# led_driver_12v_1a_round.net
KiCad netlist of a schematic drawn in EAGLE
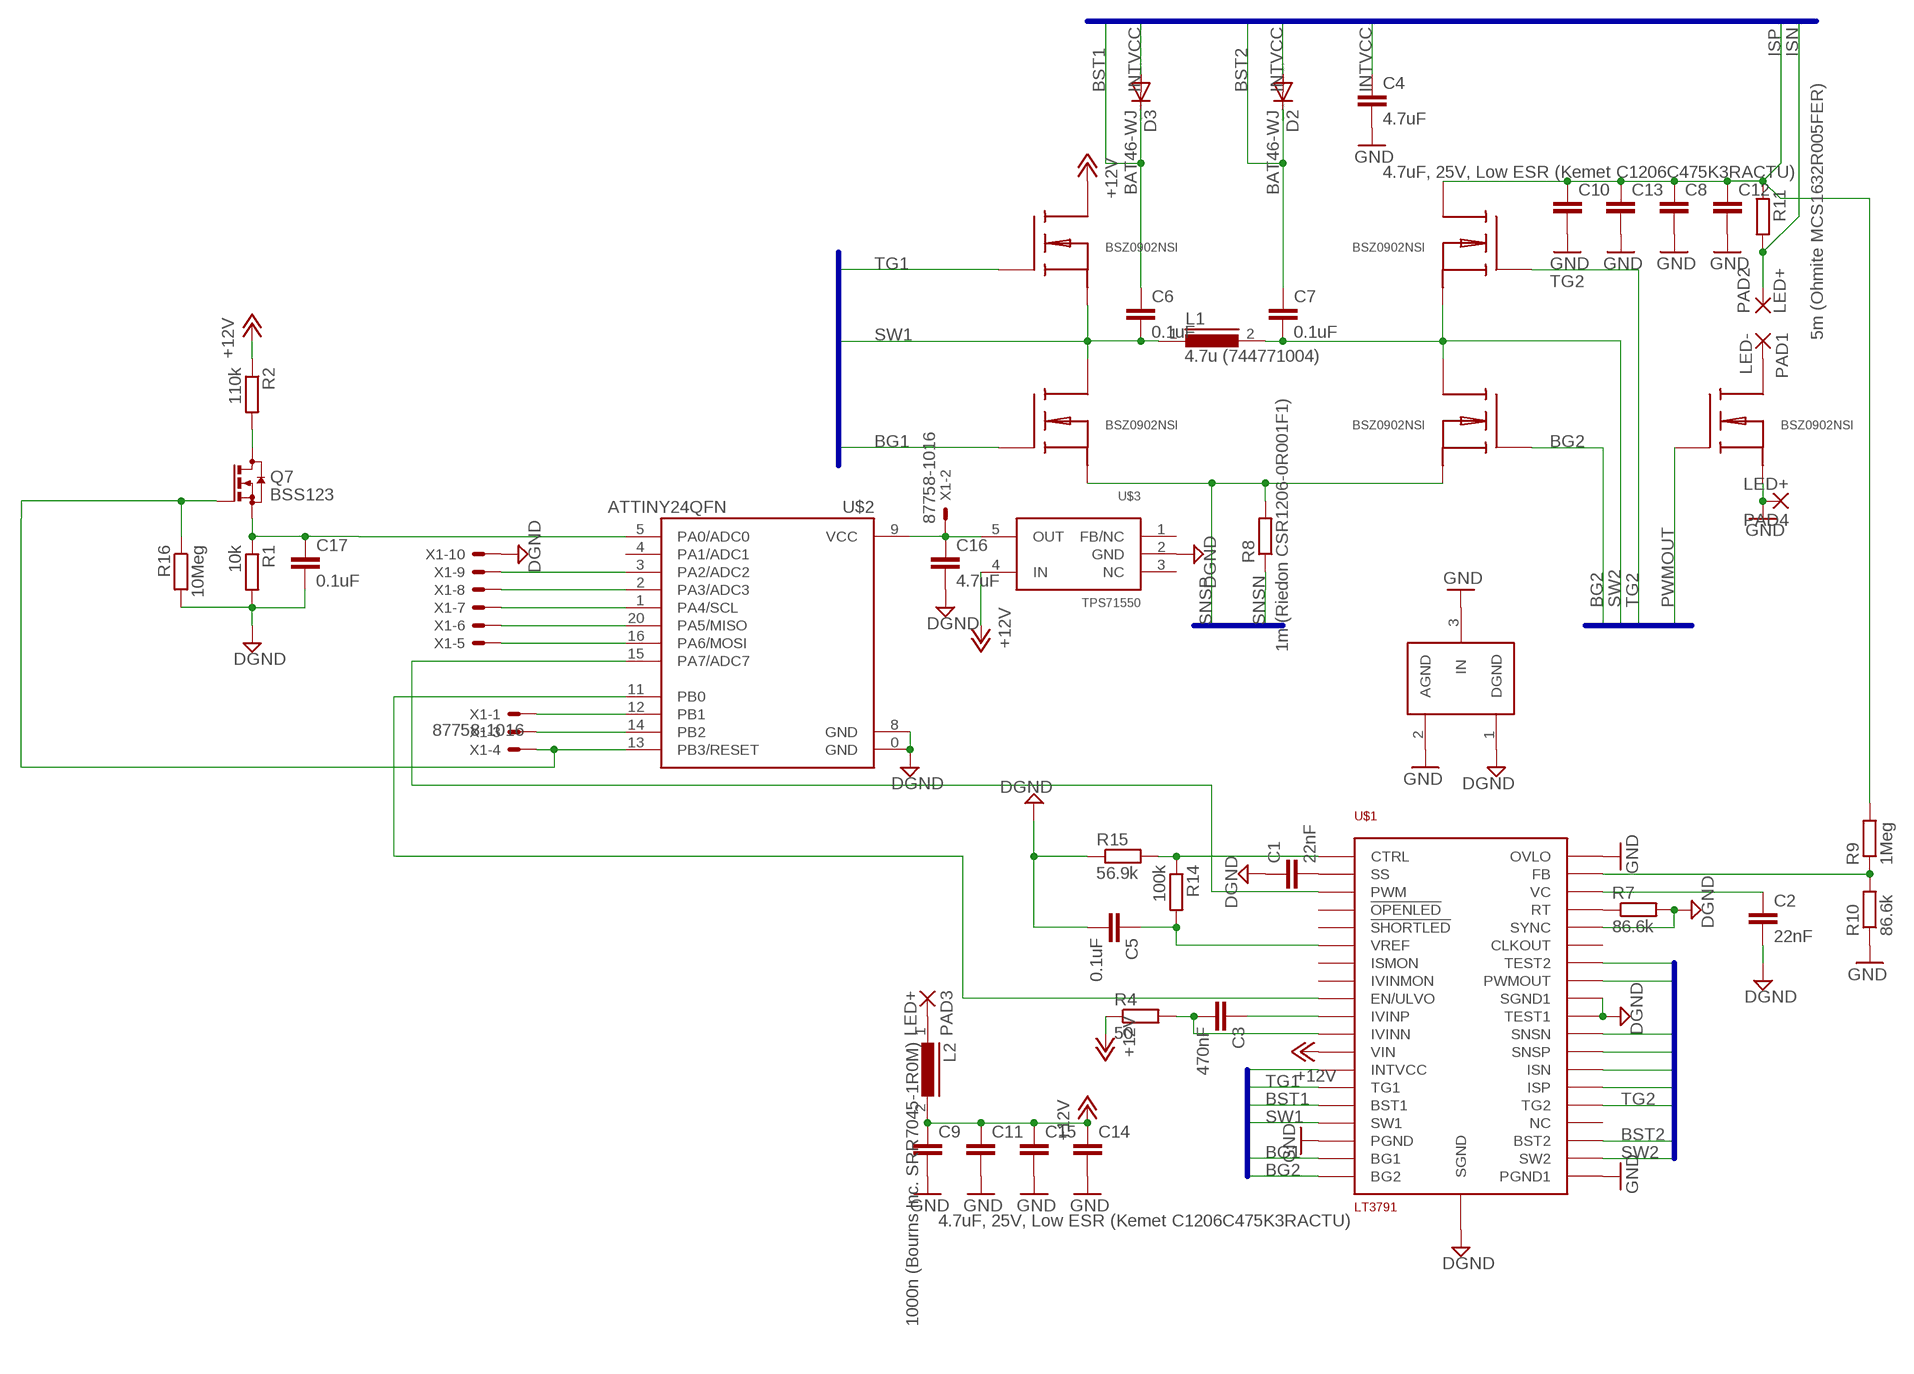
[diagram p0: schematic, sheet 1]

(export (version "E")
  (design (tool "Eeschema 10.0.6"))
  (components
    (comp (ref "C1")
      (value "22nF")
      (footprint "eagle-import:C0402")
      (libsource (lib "eagle-import") (part "resistor_C-EUC0402"))
    )
    (comp (ref "C2")
      (value "22nF")
      (footprint "eagle-import:C0402K")
      (libsource (lib "eagle-import") (part "resistor_C-EUC0402K"))
    )
    (comp (ref "C3")
      (value "470nF")
      (footprint "eagle-import:C0402K")
      (libsource (lib "eagle-import") (part "resistor_C-EUC0402K"))
    )
    (comp (ref "C4")
      (value "4.7uF")
      (footprint "eagle-import:C1206")
      (libsource (lib "eagle-import") (part "C-EUC1206"))
    )
    (comp (ref "C5")
      (value "0.1uF")
      (footprint "eagle-import:C0402K")
      (libsource (lib "eagle-import") (part "resistor_C-EUC0402K"))
    )
    (comp (ref "C6")
      (value "0.1uF")
      (footprint "eagle-import:C0402K")
      (libsource (lib "eagle-import") (part "resistor_C-EUC0402K"))
    )
    (comp (ref "C7")
      (value "0.1uF")
      (footprint "eagle-import:C0402K")
      (libsource (lib "eagle-import") (part "resistor_C-EUC0402K"))
    )
    (comp (ref "C8")
      (value "4.7uF, 25V, Low ESR (Kemet C1206C475K3RACTU)")
      (footprint "eagle-import:C1206")
      (libsource (lib "eagle-import") (part "C-EUC1206"))
    )
    (comp (ref "C9")
      (value "4.7uF, 25V, Low ESR (Kemet C1206C475K3RACTU)")
      (footprint "eagle-import:C1206")
      (libsource (lib "eagle-import") (part "C-EUC1206"))
    )
    (comp (ref "C10")
      (value "4.7uF, 25V, Low ESR (Kemet C1206C475K3RACTU)")
      (footprint "eagle-import:C1206")
      (libsource (lib "eagle-import") (part "C-EUC1206"))
    )
    (comp (ref "C11")
      (value "4.7uF, 25V, Low ESR (Kemet C1206C475K3RACTU)")
      (footprint "eagle-import:C1206")
      (libsource (lib "eagle-import") (part "C-EUC1206"))
    )
    (comp (ref "C12")
      (value "4.7uF, 25V, Low ESR (Kemet C1206C475K3RACTU)")
      (footprint "eagle-import:C1206")
      (libsource (lib "eagle-import") (part "C-EUC1206"))
    )
    (comp (ref "C13")
      (value "4.7uF, 25V, Low ESR (Kemet C1206C475K3RACTU)")
      (footprint "eagle-import:C1206")
      (libsource (lib "eagle-import") (part "C-EUC1206"))
    )
    (comp (ref "C14")
      (value "4.7uF, 25V, Low ESR (Kemet C1206C475K3RACTU)")
      (footprint "eagle-import:C1206")
      (libsource (lib "eagle-import") (part "C-EUC1206"))
    )
    (comp (ref "C15")
      (value "4.7uF, 25V, Low ESR (Kemet C1206C475K3RACTU)")
      (footprint "eagle-import:C1206")
      (libsource (lib "eagle-import") (part "C-EUC1206"))
    )
    (comp (ref "C16")
      (value "4.7uF")
      (footprint "eagle-import:C1206")
      (libsource (lib "eagle-import") (part "C-EUC1206"))
    )
    (comp (ref "C17")
      (value "0.1uF")
      (footprint "eagle-import:C0402K")
      (libsource (lib "eagle-import") (part "resistor_C-EUC0402K"))
    )
    (comp (ref "D2")
      (value "BAT46-WJ")
      (footprint "eagle-import:SOD323-W")
      (libsource (lib "eagle-import") (part "DIODE-SOD323-W"))
    )
    (comp (ref "D3")
      (value "BAT46-WJ")
      (footprint "eagle-import:SOD323-W")
      (libsource (lib "eagle-import") (part "DIODE-SOD323-W"))
    )
    (comp (ref "L1")
      (value "4.7u (744771004)")
      (footprint "eagle-import:DR127")
      (libsource (lib "eagle-import") (part "DR127"))
    )
    (comp (ref "L2")
      (value "1000n (Bourns Inc. SRR7045-1R0M)")
      (footprint "eagle-import:DR74")
      (libsource (lib "eagle-import") (part "DR74"))
    )
    (comp (ref "PAD1")
      (value "LED-")
      (footprint "eagle-import:3,81_1,4")
      (libsource (lib "eagle-import") (part "WIREPAD3,81/1,4"))
    )
    (comp (ref "PAD2")
      (value "LED+")
      (footprint "eagle-import:3,81_1,4")
      (libsource (lib "eagle-import") (part "WIREPAD3,81/1,4"))
    )
    (comp (ref "PAD3")
      (value "LED+")
      (footprint "eagle-import:5-2,5")
      (libsource (lib "eagle-import") (part "WIREPADSMD5-2,5"))
    )
    (comp (ref "PAD4")
      (value "LED+")
      (footprint "eagle-import:5-2,5")
      (libsource (lib "eagle-import") (part "WIREPADSMD5-2,5"))
    )
    (comp (ref "Q1")
      (value "BSZ0902NSI")
      (footprint "eagle-import:BSZ090X")
      (libsource (lib "eagle-import") (part "BSZ090X"))
    )
    (comp (ref "Q2")
      (value "BSZ0902NSI")
      (footprint "eagle-import:BSZ090X")
      (libsource (lib "eagle-import") (part "BSZ090X"))
    )
    (comp (ref "Q3")
      (value "BSZ0902NSI")
      (footprint "eagle-import:BSZ090X")
      (libsource (lib "eagle-import") (part "BSZ090X"))
    )
    (comp (ref "Q4")
      (value "BSZ0902NSI")
      (footprint "eagle-import:BSZ090X")
      (libsource (lib "eagle-import") (part "BSZ090X"))
    )
    (comp (ref "Q5")
      (value "BSZ0902NSI")
      (footprint "eagle-import:BSZ090X")
      (libsource (lib "eagle-import") (part "BSZ090X"))
    )
    (comp (ref "Q7")
      (value "BSS123")
      (footprint "eagle-import:SOT23")
      (libsource (lib "eagle-import") (part "BSS123"))
    )
    (comp (ref "R1")
      (value "10k")
      (footprint "eagle-import:R0402")
      (libsource (lib "eagle-import") (part "R-EU_R0402"))
    )
    (comp (ref "R2")
      (value "110k")
      (footprint "eagle-import:R0402")
      (libsource (lib "eagle-import") (part "R-EU_R0402"))
    )
    (comp (ref "R4")
      (value "50")
      (footprint "eagle-import:R0402")
      (libsource (lib "eagle-import") (part "R-EU_R0402"))
    )
    (comp (ref "R7")
      (value "86.6k")
      (footprint "eagle-import:R0402")
      (libsource (lib "eagle-import") (part "R-EU_R0402"))
    )
    (comp (ref "R8")
      (value "1m (Riedon CSR1206-0R001F1)")
      (footprint "eagle-import:R1206")
      (libsource (lib "eagle-import") (part "R-EU_R1206"))
    )
    (comp (ref "R9")
      (value "1Meg")
      (footprint "eagle-import:R0402")
      (libsource (lib "eagle-import") (part "R-EU_R0402"))
    )
    (comp (ref "R10")
      (value "86.6k")
      (footprint "eagle-import:R0402")
      (libsource (lib "eagle-import") (part "R-EU_R0402"))
    )
    (comp (ref "R11")
      (value "5m (Ohmite MCS1632R005FER)")
      (footprint "eagle-import:R1206")
      (libsource (lib "eagle-import") (part "R-EU_R1206"))
    )
    (comp (ref "R14")
      (value "100k")
      (footprint "eagle-import:R0402")
      (libsource (lib "eagle-import") (part "R-EU_R0402"))
    )
    (comp (ref "R15")
      (value "56.9k")
      (footprint "eagle-import:R0402")
      (libsource (lib "eagle-import") (part "R-EU_R0402"))
    )
    (comp (ref "R16")
      (value "10Meg")
      (footprint "eagle-import:R0402")
      (libsource (lib "eagle-import") (part "R-EU_R0402"))
    )
    (comp (ref "U$1")
      (value "LT3791")
      (footprint "eagle-import:TSSOP38")
      (libsource (lib "eagle-import") (part "LT3791"))
    )
    (comp (ref "U$2")
      (value "ATTINY24QFN")
      (footprint "eagle-import:QFN20")
      (libsource (lib "eagle-import") (part "ATTINY24QFN"))
    )
    (comp (ref "U$3")
      (value "TPS71550")
      (footprint "eagle-import:SC70")
      (libsource (lib "eagle-import") (part "TPS715"))
    )
    (comp (ref "U$4")
      (value "GND_CONNECT")
      (footprint "eagle-import:GND_CONNECT")
      (libsource (lib "eagle-import") (part "GND_CONNECT"))
    )
    (comp (ref "X1")
      (value "87758-1016")
      (footprint "eagle-import:87758-1016")
      (fields (field (name "MF") "MOLEX"))
      (libsource (lib "eagle-import") (part "87758-1016"))
    )
  )
  (nets
    (net (code "1") (name "+12V") (class "Default")
      (node (ref "C11") (pin "1") (pinfunction "1_1") (pintype "passive"))
      (node (ref "C14") (pin "1") (pinfunction "1_1") (pintype "passive"))
      (node (ref "C15") (pin "1") (pinfunction "1_1") (pintype "passive"))
      (node (ref "C9") (pin "1") (pinfunction "1_1") (pintype "passive"))
      (node (ref "L2") (pin "2") (pinfunction "2_2") (pintype "passive"))
      (node (ref "Q1") (pin "D") (pinfunction "D_D") (pintype "bidirectional"))
      (node (ref "Q1") (pin "D@1") (pinfunction "D_D@1") (pintype "bidirectional"))
      (node (ref "Q1") (pin "D@2") (pinfunction "D_D@2") (pintype "bidirectional"))
      (node (ref "Q1") (pin "D@3") (pinfunction "D_D@3") (pintype "bidirectional"))
      (node (ref "Q1") (pin "D@4") (pinfunction "D_D@4") (pintype "bidirectional"))
      (node (ref "R2") (pin "1") (pinfunction "1_1") (pintype "passive"))
      (node (ref "R4") (pin "1") (pinfunction "1_1") (pintype "passive"))
      (node (ref "U$1") (pin "P$12") (pinfunction "VIN_P$12") (pintype "bidirectional"))
      (node (ref "U$3") (pin "4") (pinfunction "IN_4") (pintype "bidirectional"))
    )
    (net (code "3") (name "BG1") (class "Default")
      (node (ref "Q2") (pin "G") (pinfunction "G_G") (pintype "bidirectional"))
      (node (ref "U$1") (pin "P$18") (pinfunction "BG1_P$18") (pintype "bidirectional"))
    )
    (net (code "4") (name "BG2") (class "Default")
      (node (ref "Q3") (pin "G") (pinfunction "G_G") (pintype "bidirectional"))
      (node (ref "U$1") (pin "P$19") (pinfunction "BG2_P$19") (pintype "bidirectional"))
    )
    (net (code "5") (name "BST1") (class "Default")
      (node (ref "C6") (pin "1") (pinfunction "1_1") (pintype "passive"))
      (node (ref "D3") (pin "C") (pinfunction "C_C") (pintype "passive"))
      (node (ref "U$1") (pin "P$15") (pinfunction "BST1_P$15") (pintype "bidirectional"))
    )
    (net (code "6") (name "BST2") (class "Default")
      (node (ref "C7") (pin "1") (pinfunction "1_1") (pintype "passive"))
      (node (ref "D2") (pin "C") (pinfunction "C_C") (pintype "passive"))
      (node (ref "U$1") (pin "P$22") (pinfunction "BST2_P$22") (pintype "bidirectional"))
    )
    (net (code "7") (name "DGND") (class "Default")
      (node (ref "C1") (pin "1") (pinfunction "1_1") (pintype "passive"))
      (node (ref "C16") (pin "2") (pinfunction "2_2") (pintype "passive"))
      (node (ref "C17") (pin "2") (pinfunction "2_2") (pintype "passive"))
      (node (ref "C2") (pin "2") (pinfunction "2_2") (pintype "passive"))
      (node (ref "C5") (pin "2") (pinfunction "2_2") (pintype "passive"))
      (node (ref "R1") (pin "2") (pinfunction "2_2") (pintype "passive"))
      (node (ref "R15") (pin "1") (pinfunction "1_1") (pintype "passive"))
      (node (ref "R16") (pin "2") (pinfunction "2_2") (pintype "passive"))
      (node (ref "R7") (pin "2") (pinfunction "2_2") (pintype "passive"))
      (node (ref "U$1") (pin "P$29") (pinfunction "TEST1_P$29") (pintype "bidirectional"))
      (node (ref "U$1") (pin "P$30") (pinfunction "SGND_P$30") (pintype "bidirectional"))
      (node (ref "U$1") (pin "P$34") (pinfunction "SYNC_P$34") (pintype "bidirectional"))
      (node (ref "U$1") (pin "P$39") (pinfunction "SGND1_P$39") (pintype "bidirectional"))
      (node (ref "U$2") (pin "0") (pinfunction "GND_0") (pintype "bidirectional"))
      (node (ref "U$2") (pin "8") (pinfunction "GND_8") (pintype "bidirectional"))
      (node (ref "U$3") (pin "2") (pinfunction "GND_2") (pintype "bidirectional"))
      (node (ref "U$4") (pin "1") (pinfunction "DGND_1") (pintype "bidirectional"))
      (node (ref "X1") (pin "10") (pinfunction "S_10") (pintype "passive"))
    )
    (net (code "8") (name "GND") (class "Default")
      (node (ref "C10") (pin "2") (pinfunction "2_2") (pintype "passive"))
      (node (ref "C11") (pin "2") (pinfunction "2_2") (pintype "passive"))
      (node (ref "C12") (pin "2") (pinfunction "2_2") (pintype "passive"))
      (node (ref "C13") (pin "2") (pinfunction "2_2") (pintype "passive"))
      (node (ref "C14") (pin "2") (pinfunction "2_2") (pintype "passive"))
      (node (ref "C15") (pin "2") (pinfunction "2_2") (pintype "passive"))
      (node (ref "C4") (pin "2") (pinfunction "2_2") (pintype "passive"))
      (node (ref "C8") (pin "2") (pinfunction "2_2") (pintype "passive"))
      (node (ref "C9") (pin "2") (pinfunction "2_2") (pintype "passive"))
      (node (ref "PAD4") (pin "1") (pinfunction "P_1") (pintype "passive"))
      (node (ref "Q5") (pin "S@1") (pinfunction "S_S@1") (pintype "bidirectional"))
      (node (ref "Q5") (pin "S@2") (pinfunction "S_S@2") (pintype "bidirectional"))
      (node (ref "Q5") (pin "S@3") (pinfunction "S_S@3") (pintype "bidirectional"))
      (node (ref "Q5") (pin "S@4") (pinfunction "S_S@4") (pintype "bidirectional"))
      (node (ref "R10") (pin "1") (pinfunction "1_1") (pintype "passive"))
      (node (ref "U$1") (pin "P$17") (pinfunction "PGND_P$17") (pintype "bidirectional"))
      (node (ref "U$1") (pin "P$20") (pinfunction "PGND1_P$20") (pintype "bidirectional"))
      (node (ref "U$1") (pin "P$38") (pinfunction "OVLO_P$38") (pintype "bidirectional"))
      (node (ref "U$4") (pin "2") (pinfunction "AGND_2") (pintype "bidirectional"))
      (node (ref "U$4") (pin "3") (pinfunction "IN_3") (pintype "bidirectional"))
    )
    (net (code "9") (name "INTVCC") (class "Default")
      (node (ref "C4") (pin "1") (pinfunction "1_1") (pintype "passive"))
      (node (ref "D2") (pin "A") (pinfunction "A_A") (pintype "passive"))
      (node (ref "D3") (pin "A") (pinfunction "A_A") (pintype "passive"))
      (node (ref "U$1") (pin "P$13") (pinfunction "INTVCC_P$13") (pintype "bidirectional"))
      (node (ref "U$1") (pin "P$32") (pinfunction "TEST2_P$32") (pintype "bidirectional"))
    )
    (net (code "10") (name "ISN") (class "Default")
      (node (ref "PAD2") (pin "1") (pinfunction "P_1") (pintype "passive"))
      (node (ref "R11") (pin "2") (pinfunction "2_2") (pintype "passive"))
      (node (ref "U$1") (pin "P$26") (pinfunction "ISN_P$26") (pintype "bidirectional"))
    )
    (net (code "11") (name "ISP") (class "Default")
      (node (ref "C10") (pin "1") (pinfunction "1_1") (pintype "passive"))
      (node (ref "C12") (pin "1") (pinfunction "1_1") (pintype "passive"))
      (node (ref "C13") (pin "1") (pinfunction "1_1") (pintype "passive"))
      (node (ref "C8") (pin "1") (pinfunction "1_1") (pintype "passive"))
      (node (ref "Q4") (pin "D") (pinfunction "D_D") (pintype "bidirectional"))
      (node (ref "Q4") (pin "D@1") (pinfunction "D_D@1") (pintype "bidirectional"))
      (node (ref "Q4") (pin "D@2") (pinfunction "D_D@2") (pintype "bidirectional"))
      (node (ref "Q4") (pin "D@3") (pinfunction "D_D@3") (pintype "bidirectional"))
      (node (ref "Q4") (pin "D@4") (pinfunction "D_D@4") (pintype "bidirectional"))
      (node (ref "R11") (pin "1") (pinfunction "1_1") (pintype "passive"))
      (node (ref "R9") (pin "2") (pinfunction "2_2") (pintype "passive"))
      (node (ref "U$1") (pin "P$25") (pinfunction "ISP_P$25") (pintype "bidirectional"))
    )
    (net (code "12") (name "Net-(PAD1-P)") (class "Default")
      (node (ref "PAD1") (pin "1") (pinfunction "P_1") (pintype "passive"))
      (node (ref "Q5") (pin "D") (pinfunction "D_D") (pintype "bidirectional"))
      (node (ref "Q5") (pin "D@1") (pinfunction "D_D@1") (pintype "bidirectional"))
      (node (ref "Q5") (pin "D@2") (pinfunction "D_D@2") (pintype "bidirectional"))
      (node (ref "Q5") (pin "D@3") (pinfunction "D_D@3") (pintype "bidirectional"))
      (node (ref "Q5") (pin "D@4") (pinfunction "D_D@4") (pintype "bidirectional"))
    )
    (net (code "13") (name "Net-(PAD3-P)") (class "Default")
      (node (ref "L2") (pin "1") (pinfunction "1_1") (pintype "passive"))
      (node (ref "PAD3") (pin "1") (pinfunction "P_1") (pintype "passive"))
    )
    (net (code "14") (name "Net-(Q7-D)") (class "Default")
      (node (ref "Q7") (pin "3") (pinfunction "D_3") (pintype "passive"))
      (node (ref "R2") (pin "2") (pinfunction "2_2") (pintype "passive"))
    )
    (net (code "15") (name "Net-(Q7-G)") (class "Default")
      (node (ref "Q7") (pin "1") (pinfunction "G_1") (pintype "passive"))
      (node (ref "R16") (pin "1") (pinfunction "1_1") (pintype "passive"))
      (node (ref "U$2") (pin "13") (pinfunction "PB3/RESET_13") (pintype "bidirectional"))
      (node (ref "X1") (pin "4") (pinfunction "S_4") (pintype "passive"))
    )
    (net (code "16") (name "Net-(Q7-S)") (class "Default")
      (node (ref "C17") (pin "1") (pinfunction "1_1") (pintype "passive"))
      (node (ref "Q7") (pin "2") (pinfunction "S_2") (pintype "passive"))
      (node (ref "R1") (pin "1") (pinfunction "1_1") (pintype "passive"))
      (node (ref "U$2") (pin "5") (pinfunction "PA0/ADC0_5") (pintype "bidirectional"))
    )
    (net (code "17") (name "Net-(U$1-CTRL)") (class "Default")
      (node (ref "R14") (pin "1") (pinfunction "1_1") (pintype "passive"))
      (node (ref "R15") (pin "2") (pinfunction "2_2") (pintype "passive"))
      (node (ref "U$1") (pin "P$1") (pinfunction "CTRL_P$1") (pintype "bidirectional"))
    )
    (net (code "18") (name "Net-(U$1-EN{slash}ULVO)") (class "Default")
      (node (ref "U$1") (pin "P$9") (pinfunction "EN/ULVO_P$9") (pintype "bidirectional"))
      (node (ref "U$2") (pin "11") (pinfunction "PB0_11") (pintype "bidirectional"))
    )
    (net (code "19") (name "Net-(U$1-FB)") (class "Default")
      (node (ref "R10") (pin "2") (pinfunction "2_2") (pintype "passive"))
      (node (ref "R9") (pin "1") (pinfunction "1_1") (pintype "passive"))
      (node (ref "U$1") (pin "P$37") (pinfunction "FB_P$37") (pintype "bidirectional"))
    )
    (net (code "20") (name "Net-(U$1-IVINN)") (class "Default")
      (node (ref "C3") (pin "2") (pinfunction "2_2") (pintype "passive"))
      (node (ref "R4") (pin "2") (pinfunction "2_2") (pintype "passive"))
      (node (ref "U$1") (pin "P$11") (pinfunction "IVINN_P$11") (pintype "bidirectional"))
    )
    (net (code "21") (name "Net-(U$1-IVINP)") (class "Default")
      (node (ref "C3") (pin "1") (pinfunction "1_1") (pintype "passive"))
      (node (ref "U$1") (pin "P$10") (pinfunction "IVINP_P$10") (pintype "bidirectional"))
    )
    (net (code "22") (name "Net-(U$1-PWM)") (class "Default")
      (node (ref "U$1") (pin "P$3") (pinfunction "PWM_P$3") (pintype "bidirectional"))
      (node (ref "U$2") (pin "15") (pinfunction "PA7/ADC7_15") (pintype "bidirectional"))
    )
    (net (code "23") (name "Net-(U$1-RT)") (class "Default")
      (node (ref "R7") (pin "1") (pinfunction "1_1") (pintype "passive"))
      (node (ref "U$1") (pin "P$35") (pinfunction "RT_P$35") (pintype "bidirectional"))
    )
    (net (code "24") (name "Net-(U$1-SS)") (class "Default")
      (node (ref "C1") (pin "2") (pinfunction "2_2") (pintype "passive"))
      (node (ref "U$1") (pin "P$2") (pinfunction "SS_P$2") (pintype "bidirectional"))
    )
    (net (code "25") (name "Net-(U$1-VC)") (class "Default")
      (node (ref "C2") (pin "1") (pinfunction "1_1") (pintype "passive"))
      (node (ref "U$1") (pin "P$36") (pinfunction "VC_P$36") (pintype "bidirectional"))
    )
    (net (code "26") (name "Net-(U$1-VREF)") (class "Default")
      (node (ref "C5") (pin "1") (pinfunction "1_1") (pintype "passive"))
      (node (ref "R14") (pin "2") (pinfunction "2_2") (pintype "passive"))
      (node (ref "U$1") (pin "P$6") (pinfunction "VREF_P$6") (pintype "bidirectional"))
    )
    (net (code "27") (name "Net-(U$2-PA2{slash}ADC2)") (class "Default")
      (node (ref "U$2") (pin "3") (pinfunction "PA2/ADC2_3") (pintype "bidirectional"))
      (node (ref "X1") (pin "9") (pinfunction "S_9") (pintype "passive"))
    )
    (net (code "28") (name "Net-(U$2-PA3{slash}ADC3)") (class "Default")
      (node (ref "U$2") (pin "2") (pinfunction "PA3/ADC3_2") (pintype "bidirectional"))
      (node (ref "X1") (pin "8") (pinfunction "S_8") (pintype "passive"))
    )
    (net (code "29") (name "Net-(U$2-PA4{slash}SCL)") (class "Default")
      (node (ref "U$2") (pin "1") (pinfunction "PA4/SCL_1") (pintype "bidirectional"))
      (node (ref "X1") (pin "7") (pinfunction "S_7") (pintype "passive"))
    )
    (net (code "30") (name "Net-(U$2-PA5{slash}MISO)") (class "Default")
      (node (ref "U$2") (pin "20") (pinfunction "PA5/MISO_20") (pintype "bidirectional"))
      (node (ref "X1") (pin "6") (pinfunction "S_6") (pintype "passive"))
    )
    (net (code "31") (name "Net-(U$2-PA6{slash}MOSI)") (class "Default")
      (node (ref "U$2") (pin "16") (pinfunction "PA6/MOSI_16") (pintype "bidirectional"))
      (node (ref "X1") (pin "5") (pinfunction "S_5") (pintype "passive"))
    )
    (net (code "32") (name "Net-(U$2-PB1)") (class "Default")
      (node (ref "U$2") (pin "12") (pinfunction "PB1_12") (pintype "bidirectional"))
      (node (ref "X1") (pin "1") (pinfunction "S_1") (pintype "passive"))
    )
    (net (code "33") (name "Net-(U$2-PB2)") (class "Default")
      (node (ref "U$2") (pin "14") (pinfunction "PB2_14") (pintype "bidirectional"))
      (node (ref "X1") (pin "3") (pinfunction "S_3") (pintype "passive"))
    )
    (net (code "34") (name "Net-(U$2-VCC)") (class "Default")
      (node (ref "C16") (pin "1") (pinfunction "1_1") (pintype "passive"))
      (node (ref "U$2") (pin "9") (pinfunction "VCC_9") (pintype "bidirectional"))
      (node (ref "U$3") (pin "5") (pinfunction "OUT_5") (pintype "bidirectional"))
      (node (ref "X1") (pin "2") (pinfunction "S_2") (pintype "passive"))
    )
    (net (code "35") (name "PWMOUT") (class "Default")
      (node (ref "Q5") (pin "G") (pinfunction "G_G") (pintype "bidirectional"))
      (node (ref "U$1") (pin "P$31") (pinfunction "PWMOUT_P$31") (pintype "bidirectional"))
    )
    (net (code "36") (name "SNSN") (class "Default")
      (node (ref "R8") (pin "1") (pinfunction "1_1") (pintype "passive"))
      (node (ref "U$1") (pin "P$28") (pinfunction "SNSN_P$28") (pintype "bidirectional"))
    )
    (net (code "37") (name "SNSP") (class "Default")
      (node (ref "Q2") (pin "S@1") (pinfunction "S_S@1") (pintype "bidirectional"))
      (node (ref "Q2") (pin "S@2") (pinfunction "S_S@2") (pintype "bidirectional"))
      (node (ref "Q2") (pin "S@3") (pinfunction "S_S@3") (pintype "bidirectional"))
      (node (ref "Q2") (pin "S@4") (pinfunction "S_S@4") (pintype "bidirectional"))
      (node (ref "Q3") (pin "S@1") (pinfunction "S_S@1") (pintype "bidirectional"))
      (node (ref "Q3") (pin "S@2") (pinfunction "S_S@2") (pintype "bidirectional"))
      (node (ref "Q3") (pin "S@3") (pinfunction "S_S@3") (pintype "bidirectional"))
      (node (ref "Q3") (pin "S@4") (pinfunction "S_S@4") (pintype "bidirectional"))
      (node (ref "R8") (pin "2") (pinfunction "2_2") (pintype "passive"))
      (node (ref "U$1") (pin "P$27") (pinfunction "SNSP_P$27") (pintype "bidirectional"))
    )
    (net (code "38") (name "SW1") (class "Default")
      (node (ref "C6") (pin "2") (pinfunction "2_2") (pintype "passive"))
      (node (ref "L1") (pin "1") (pinfunction "1_1") (pintype "passive"))
      (node (ref "Q1") (pin "S@1") (pinfunction "S_S@1") (pintype "bidirectional"))
      (node (ref "Q1") (pin "S@2") (pinfunction "S_S@2") (pintype "bidirectional"))
      (node (ref "Q1") (pin "S@3") (pinfunction "S_S@3") (pintype "bidirectional"))
      (node (ref "Q1") (pin "S@4") (pinfunction "S_S@4") (pintype "bidirectional"))
      (node (ref "Q2") (pin "D") (pinfunction "D_D") (pintype "bidirectional"))
      (node (ref "Q2") (pin "D@1") (pinfunction "D_D@1") (pintype "bidirectional"))
      (node (ref "Q2") (pin "D@2") (pinfunction "D_D@2") (pintype "bidirectional"))
      (node (ref "Q2") (pin "D@3") (pinfunction "D_D@3") (pintype "bidirectional"))
      (node (ref "Q2") (pin "D@4") (pinfunction "D_D@4") (pintype "bidirectional"))
      (node (ref "U$1") (pin "P$16") (pinfunction "SW1_P$16") (pintype "bidirectional"))
    )
    (net (code "39") (name "SW2") (class "Default")
      (node (ref "C7") (pin "2") (pinfunction "2_2") (pintype "passive"))
      (node (ref "L1") (pin "2") (pinfunction "2_2") (pintype "passive"))
      (node (ref "Q3") (pin "D") (pinfunction "D_D") (pintype "bidirectional"))
      (node (ref "Q3") (pin "D@1") (pinfunction "D_D@1") (pintype "bidirectional"))
      (node (ref "Q3") (pin "D@2") (pinfunction "D_D@2") (pintype "bidirectional"))
      (node (ref "Q3") (pin "D@3") (pinfunction "D_D@3") (pintype "bidirectional"))
      (node (ref "Q3") (pin "D@4") (pinfunction "D_D@4") (pintype "bidirectional"))
      (node (ref "Q4") (pin "S@1") (pinfunction "S_S@1") (pintype "bidirectional"))
      (node (ref "Q4") (pin "S@2") (pinfunction "S_S@2") (pintype "bidirectional"))
      (node (ref "Q4") (pin "S@3") (pinfunction "S_S@3") (pintype "bidirectional"))
      (node (ref "Q4") (pin "S@4") (pinfunction "S_S@4") (pintype "bidirectional"))
      (node (ref "U$1") (pin "P$21") (pinfunction "SW2_P$21") (pintype "bidirectional"))
    )
    (net (code "40") (name "TG1") (class "Default")
      (node (ref "Q1") (pin "G") (pinfunction "G_G") (pintype "bidirectional"))
      (node (ref "U$1") (pin "P$14") (pinfunction "TG1_P$14") (pintype "bidirectional"))
    )
    (net (code "41") (name "TG2") (class "Default")
      (node (ref "Q4") (pin "G") (pinfunction "G_G") (pintype "bidirectional"))
      (node (ref "U$1") (pin "P$24") (pinfunction "TG2_P$24") (pintype "bidirectional"))
    )
    (net (code "42") (name "unconnected-(U$1-CLKOUT-PadP$33)") (class "Default")
      (node (ref "U$1") (pin "P$33") (pinfunction "CLKOUT_P$33") (pintype "bidirectional"))
    )
    (net (code "43") (name "unconnected-(U$1-ISMON-PadP$7)") (class "Default")
      (node (ref "U$1") (pin "P$7") (pinfunction "ISMON_P$7") (pintype "bidirectional"))
    )
    (net (code "44") (name "unconnected-(U$1-IVINMON-PadP$8)") (class "Default")
      (node (ref "U$1") (pin "P$8") (pinfunction "IVINMON_P$8") (pintype "bidirectional"))
    )
    (net (code "45") (name "unconnected-(U$1-NC-PadP$23)") (class "Default")
      (node (ref "U$1") (pin "P$23") (pinfunction "NC_P$23") (pintype "bidirectional"))
    )
    (net (code "46") (name "unconnected-(U$1-~{OPENLED}-PadP$4)") (class "Default")
      (node (ref "U$1") (pin "P$4") (pinfunction "~{OPENLED}_P$4") (pintype "bidirectional"))
    )
    (net (code "47") (name "unconnected-(U$1-~{SHORTLED}-PadP$5)") (class "Default")
      (node (ref "U$1") (pin "P$5") (pinfunction "~{SHORTLED}_P$5") (pintype "bidirectional"))
    )
    (net (code "48") (name "unconnected-(U$2-PA1{slash}ADC1-Pad4)") (class "Default")
      (node (ref "U$2") (pin "4") (pinfunction "PA1/ADC1_4") (pintype "bidirectional"))
    )
    (net (code "49") (name "unconnected-(U$3-FB{slash}NC-Pad1)") (class "Default")
      (node (ref "U$3") (pin "1") (pinfunction "FB/NC_1") (pintype "bidirectional"))
    )
    (net (code "50") (name "unconnected-(U$3-NC-Pad3)") (class "Default")
      (node (ref "U$3") (pin "3") (pinfunction "NC_3") (pintype "bidirectional"))
    )
  )
)
